# ir_remote_v2.net
KiCad netlist of a schematic drawn in EAGLE
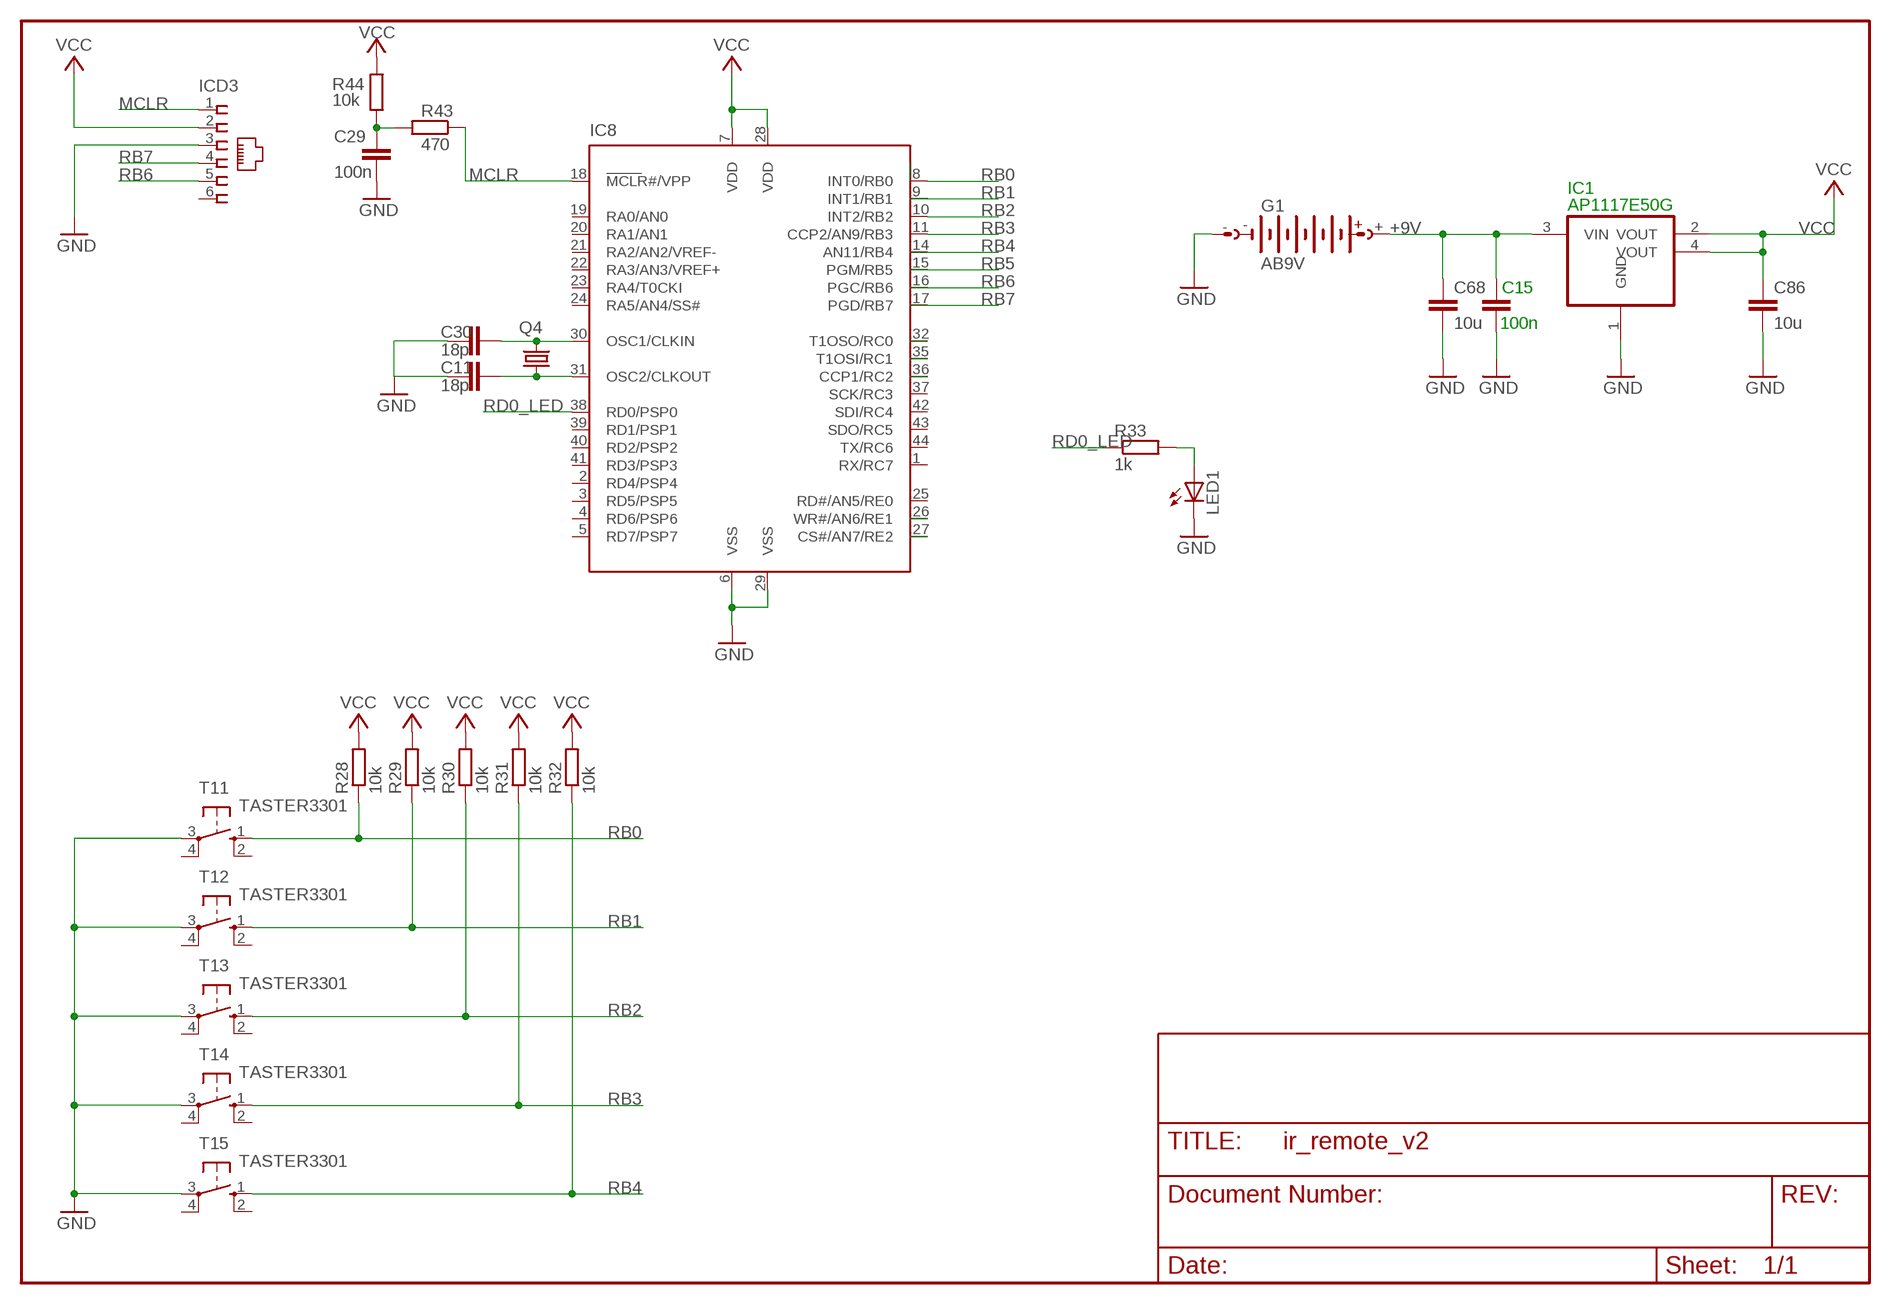
[diagram p0: schematic, sheet 1]

(export (version "E")
  (design (tool "Eeschema 10.0.6"))
  (components
    (comp (ref "C11")
      (value "18p")
      (footprint "eagle-import:C0805")
      (libsource (lib "eagle-import") (part "C-EUC0805"))
    )
    (comp (ref "C15")
      (value "100n")
      (footprint "eagle-import:C0805")
      (libsource (lib "eagle-import") (part "rcl_416_C-EUC0805"))
    )
    (comp (ref "C29")
      (value "100n")
      (footprint "eagle-import:C0805")
      (libsource (lib "eagle-import") (part "C-EUC0805"))
    )
    (comp (ref "C30")
      (value "18p")
      (footprint "eagle-import:C0805")
      (libsource (lib "eagle-import") (part "C-EUC0805"))
    )
    (comp (ref "C68")
      (value "10u")
      (footprint "eagle-import:C0805")
      (libsource (lib "eagle-import") (part "C-EUC0805"))
    )
    (comp (ref "C86")
      (value "10u")
      (footprint "eagle-import:C0805")
      (libsource (lib "eagle-import") (part "C-EUC0805"))
    )
    (comp (ref "G1")
      (value "AB9V")
      (footprint "eagle-import:AB9V")
      (libsource (lib "eagle-import") (part "AB9V"))
    )
    (comp (ref "IC1")
      (value "AP1117E50G")
      (footprint "eagle-import:SOT223")
      (libsource (lib "eagle-import") (part "REG1117-2OUT"))
    )
    (comp (ref "IC8")
      (value "PIC18F4520")
      (footprint "eagle-import:TQFP44")
      (libsource (lib "eagle-import") (part "PIC18F4520"))
    )
    (comp (ref "ICD3")
      (value "520250-3")
      (footprint "eagle-import:520250-3")
      (libsource (lib "eagle-import") (part "520250-3"))
    )
    (comp (ref "LED1")
      (value "LED5MM")
      (footprint "eagle-import:LED5MM")
      (libsource (lib "eagle-import") (part "LED5MM"))
    )
    (comp (ref "Q4")
      (value "CRYTALHC49U-V")
      (footprint "eagle-import:HC49U-V")
      (libsource (lib "eagle-import") (part "CRYTALHC49U-V"))
    )
    (comp (ref "R28")
      (value "10k")
      (footprint "eagle-import:0207_7")
      (libsource (lib "eagle-import") (part "R-EU_0207/7"))
    )
    (comp (ref "R29")
      (value "10k")
      (footprint "eagle-import:0207_7")
      (libsource (lib "eagle-import") (part "R-EU_0207/7"))
    )
    (comp (ref "R30")
      (value "10k")
      (footprint "eagle-import:0207_7")
      (libsource (lib "eagle-import") (part "R-EU_0207/7"))
    )
    (comp (ref "R31")
      (value "10k")
      (footprint "eagle-import:0207_7")
      (libsource (lib "eagle-import") (part "R-EU_0207/7"))
    )
    (comp (ref "R32")
      (value "10k")
      (footprint "eagle-import:0207_7")
      (libsource (lib "eagle-import") (part "R-EU_0207/7"))
    )
    (comp (ref "R33")
      (value "1k")
      (footprint "eagle-import:0207_10")
      (libsource (lib "eagle-import") (part "resistor_R-EU_0207/10"))
    )
    (comp (ref "R43")
      (value "470")
      (footprint "eagle-import:M0805")
      (libsource (lib "eagle-import") (part "R-EU_M0805"))
    )
    (comp (ref "R44")
      (value "10k")
      (footprint "eagle-import:M0805")
      (libsource (lib "eagle-import") (part "R-EU_M0805"))
    )
    (comp (ref "T11")
      (value "TASTER3301")
      (footprint "eagle-import:TASTER3301")
      (libsource (lib "eagle-import") (part "TASTER3301"))
    )
    (comp (ref "T12")
      (value "TASTER3301")
      (footprint "eagle-import:TASTER3301")
      (libsource (lib "eagle-import") (part "TASTER3301"))
    )
    (comp (ref "T13")
      (value "TASTER3301")
      (footprint "eagle-import:TASTER3301")
      (libsource (lib "eagle-import") (part "TASTER3301"))
    )
    (comp (ref "T14")
      (value "TASTER3301")
      (footprint "eagle-import:TASTER3301")
      (libsource (lib "eagle-import") (part "TASTER3301"))
    )
    (comp (ref "T15")
      (value "TASTER3301")
      (footprint "eagle-import:TASTER3301")
      (libsource (lib "eagle-import") (part "TASTER3301"))
    )
  )
  (nets
    (net (code "1") (name "/+9V") (class "Default")
      (node (ref "C15") (pin "1") (pinfunction "1_1") (pintype "passive"))
      (node (ref "C68") (pin "1") (pinfunction "1_1") (pintype "passive"))
      (node (ref "G1") (pin "+") (pinfunction "+_+") (pintype "passive"))
      (node (ref "IC1") (pin "3") (pinfunction "VIN_3") (pintype "input"))
    )
    (net (code "2") (name "/MCLR") (class "Default")
      (node (ref "IC8") (pin "18") (pinfunction "MCLR#/VPP_18") (pintype "input"))
      (node (ref "ICD3") (pin "1") (pinfunction "1_1") (pintype "passive"))
      (node (ref "R43") (pin "1") (pinfunction "1_1") (pintype "passive"))
    )
    (net (code "3") (name "/RB0") (class "Default")
      (node (ref "IC8") (pin "8") (pinfunction "INT0/RB0_8") (pintype "bidirectional"))
      (node (ref "R28") (pin "1") (pinfunction "1_1") (pintype "passive"))
      (node (ref "T11") (pin "1") (pinfunction "S_1") (pintype "passive"))
    )
    (net (code "4") (name "/RB1") (class "Default")
      (node (ref "IC8") (pin "35") (pinfunction "T1OSI/RC1_35") (pintype "bidirectional"))
      (node (ref "IC8") (pin "9") (pinfunction "INT1/RB1_9") (pintype "bidirectional"))
      (node (ref "R29") (pin "1") (pinfunction "1_1") (pintype "passive"))
      (node (ref "T12") (pin "1") (pinfunction "S_1") (pintype "passive"))
    )
    (net (code "5") (name "/RB2") (class "Default")
      (node (ref "IC8") (pin "10") (pinfunction "INT2/RB2_10") (pintype "bidirectional"))
      (node (ref "IC8") (pin "32") (pinfunction "T1OSO/RC0_32") (pintype "bidirectional"))
      (node (ref "R30") (pin "1") (pinfunction "1_1") (pintype "passive"))
      (node (ref "T13") (pin "1") (pinfunction "S_1") (pintype "passive"))
    )
    (net (code "6") (name "/RB3") (class "Default")
      (node (ref "IC8") (pin "11") (pinfunction "CCP2/AN9/RB3_11") (pintype "bidirectional"))
      (node (ref "R31") (pin "1") (pinfunction "1_1") (pintype "passive"))
      (node (ref "T14") (pin "1") (pinfunction "S_1") (pintype "passive"))
    )
    (net (code "7") (name "/RB4") (class "Default")
      (node (ref "IC8") (pin "14") (pinfunction "AN11/RB4_14") (pintype "bidirectional"))
      (node (ref "R32") (pin "1") (pinfunction "1_1") (pintype "passive"))
      (node (ref "T15") (pin "1") (pinfunction "S_1") (pintype "passive"))
    )
    (net (code "8") (name "/RB5") (class "Default")
      (node (ref "IC8") (pin "15") (pinfunction "PGM/RB5_15") (pintype "bidirectional"))
    )
    (net (code "9") (name "/RB6") (class "Default")
      (node (ref "IC8") (pin "16") (pinfunction "PGC/RB6_16") (pintype "bidirectional"))
      (node (ref "ICD3") (pin "5") (pinfunction "5_5") (pintype "passive"))
    )
    (net (code "10") (name "/RB7") (class "Default")
      (node (ref "IC8") (pin "17") (pinfunction "PGD/RB7_17") (pintype "bidirectional"))
      (node (ref "ICD3") (pin "4") (pinfunction "4_4") (pintype "passive"))
    )
    (net (code "11") (name "/RD0_LED") (class "Default")
      (node (ref "IC8") (pin "38") (pinfunction "RD0/PSP0_38") (pintype "bidirectional"))
      (node (ref "R33") (pin "1") (pinfunction "1_1") (pintype "passive"))
    )
    (net (code "12") (name "GND") (class "Default")
      (node (ref "C11") (pin "2") (pinfunction "2_2") (pintype "passive"))
      (node (ref "C15") (pin "2") (pinfunction "2_2") (pintype "passive"))
      (node (ref "C29") (pin "2") (pinfunction "2_2") (pintype "passive"))
      (node (ref "C30") (pin "2") (pinfunction "2_2") (pintype "passive"))
      (node (ref "C68") (pin "2") (pinfunction "2_2") (pintype "passive"))
      (node (ref "C86") (pin "2") (pinfunction "2_2") (pintype "passive"))
      (node (ref "G1") (pin "-") (pinfunction "-_-") (pintype "passive"))
      (node (ref "IC1") (pin "1") (pinfunction "GND_1") (pintype "power_in"))
      (node (ref "IC8") (pin "29") (pinfunction "VSS_29") (pintype "bidirectional"))
      (node (ref "IC8") (pin "6") (pinfunction "VSS_6") (pintype "bidirectional"))
      (node (ref "ICD3") (pin "3") (pinfunction "3_3") (pintype "passive"))
      (node (ref "LED1") (pin "K") (pinfunction "C_K") (pintype "passive"))
      (node (ref "T11") (pin "3") (pinfunction "P_3") (pintype "passive"))
      (node (ref "T12") (pin "3") (pinfunction "P_3") (pintype "passive"))
      (node (ref "T13") (pin "3") (pinfunction "P_3") (pintype "passive"))
      (node (ref "T14") (pin "3") (pinfunction "P_3") (pintype "passive"))
      (node (ref "T15") (pin "3") (pinfunction "P_3") (pintype "passive"))
    )
    (net (code "13") (name "Net-(C29-Pad1)") (class "Default")
      (node (ref "C29") (pin "1") (pinfunction "1_1") (pintype "passive"))
      (node (ref "R43") (pin "2") (pinfunction "2_2") (pintype "passive"))
      (node (ref "R44") (pin "2") (pinfunction "2_2") (pintype "passive"))
    )
    (net (code "14") (name "Net-(IC8-OSC1{slash}CLKIN)") (class "Default")
      (node (ref "C30") (pin "1") (pinfunction "1_1") (pintype "passive"))
      (node (ref "IC8") (pin "30") (pinfunction "OSC1/CLKIN_30") (pintype "input"))
      (node (ref "Q4") (pin "2") (pinfunction "2_2") (pintype "passive"))
    )
    (net (code "15") (name "Net-(IC8-OSC2{slash}CLKOUT)") (class "Default")
      (node (ref "C11") (pin "1") (pinfunction "1_1") (pintype "passive"))
      (node (ref "IC8") (pin "31") (pinfunction "OSC2/CLKOUT_31") (pintype "output"))
      (node (ref "Q4") (pin "1") (pinfunction "1_1") (pintype "passive"))
    )
    (net (code "16") (name "Net-(LED1-PadA)") (class "Default")
      (node (ref "LED1") (pin "A") (pinfunction "A_A") (pintype "passive"))
      (node (ref "R33") (pin "2") (pinfunction "2_2") (pintype "passive"))
    )
    (net (code "17") (name "VCC") (class "Default")
      (node (ref "C86") (pin "1") (pinfunction "1_1") (pintype "passive"))
      (node (ref "IC1") (pin "2") (pinfunction "VOUT_2") (pintype "output"))
      (node (ref "IC1") (pin "4") (pinfunction "VOUT_4") (pintype "bidirectional"))
      (node (ref "IC8") (pin "28") (pinfunction "VDD_28") (pintype "bidirectional"))
      (node (ref "IC8") (pin "7") (pinfunction "VDD_7") (pintype "bidirectional"))
      (node (ref "ICD3") (pin "2") (pinfunction "2_2") (pintype "passive"))
      (node (ref "R28") (pin "2") (pinfunction "2_2") (pintype "passive"))
      (node (ref "R29") (pin "2") (pinfunction "2_2") (pintype "passive"))
      (node (ref "R30") (pin "2") (pinfunction "2_2") (pintype "passive"))
      (node (ref "R31") (pin "2") (pinfunction "2_2") (pintype "passive"))
      (node (ref "R32") (pin "2") (pinfunction "2_2") (pintype "passive"))
      (node (ref "R44") (pin "1") (pinfunction "1_1") (pintype "passive"))
    )
    (net (code "18") (name "unconnected-(IC8-CCP1{slash}RC2-Pad36)") (class "Default")
      (node (ref "IC8") (pin "36") (pinfunction "CCP1/RC2_36") (pintype "bidirectional"))
    )
    (net (code "19") (name "unconnected-(IC8-CS#{slash}AN7{slash}RE2-Pad27)") (class "Default")
      (node (ref "IC8") (pin "27") (pinfunction "CS#/AN7/RE2_27") (pintype "bidirectional"))
    )
    (net (code "20") (name "unconnected-(IC8-RA0{slash}AN0-Pad19)") (class "Default")
      (node (ref "IC8") (pin "19") (pinfunction "RA0/AN0_19") (pintype "bidirectional"))
    )
    (net (code "21") (name "unconnected-(IC8-RA1{slash}AN1-Pad20)") (class "Default")
      (node (ref "IC8") (pin "20") (pinfunction "RA1/AN1_20") (pintype "bidirectional"))
    )
    (net (code "22") (name "unconnected-(IC8-RA2{slash}AN2{slash}VREF--Pad21)") (class "Default")
      (node (ref "IC8") (pin "21") (pinfunction "RA2/AN2/VREF-_21") (pintype "bidirectional"))
    )
    (net (code "23") (name "unconnected-(IC8-RA3{slash}AN3{slash}VREF+-Pad22)") (class "Default")
      (node (ref "IC8") (pin "22") (pinfunction "RA3/AN3/VREF+_22") (pintype "bidirectional"))
    )
    (net (code "24") (name "unconnected-(IC8-RA4{slash}T0CKI-Pad23)") (class "Default")
      (node (ref "IC8") (pin "23") (pinfunction "RA4/T0CKI_23") (pintype "bidirectional"))
    )
    (net (code "25") (name "unconnected-(IC8-RA5{slash}AN4{slash}SS#-Pad24)") (class "Default")
      (node (ref "IC8") (pin "24") (pinfunction "RA5/AN4/SS#_24") (pintype "bidirectional"))
    )
    (net (code "26") (name "unconnected-(IC8-RD#{slash}AN5{slash}RE0-Pad25)") (class "Default")
      (node (ref "IC8") (pin "25") (pinfunction "RD#/AN5/RE0_25") (pintype "bidirectional"))
    )
    (net (code "27") (name "unconnected-(IC8-RD1{slash}PSP1-Pad39)") (class "Default")
      (node (ref "IC8") (pin "39") (pinfunction "RD1/PSP1_39") (pintype "bidirectional"))
    )
    (net (code "28") (name "unconnected-(IC8-RD2{slash}PSP2-Pad40)") (class "Default")
      (node (ref "IC8") (pin "40") (pinfunction "RD2/PSP2_40") (pintype "bidirectional"))
    )
    (net (code "29") (name "unconnected-(IC8-RD3{slash}PSP3-Pad41)") (class "Default")
      (node (ref "IC8") (pin "41") (pinfunction "RD3/PSP3_41") (pintype "bidirectional"))
    )
    (net (code "30") (name "unconnected-(IC8-RD4{slash}PSP4-Pad2)") (class "Default")
      (node (ref "IC8") (pin "2") (pinfunction "RD4/PSP4_2") (pintype "bidirectional"))
    )
    (net (code "31") (name "unconnected-(IC8-RD5{slash}PSP5-Pad3)") (class "Default")
      (node (ref "IC8") (pin "3") (pinfunction "RD5/PSP5_3") (pintype "bidirectional"))
    )
    (net (code "32") (name "unconnected-(IC8-RD6{slash}PSP6-Pad4)") (class "Default")
      (node (ref "IC8") (pin "4") (pinfunction "RD6/PSP6_4") (pintype "bidirectional"))
    )
    (net (code "33") (name "unconnected-(IC8-RD7{slash}PSP7-Pad5)") (class "Default")
      (node (ref "IC8") (pin "5") (pinfunction "RD7/PSP7_5") (pintype "bidirectional"))
    )
    (net (code "34") (name "unconnected-(IC8-RX{slash}RC7-Pad1)") (class "Default")
      (node (ref "IC8") (pin "1") (pinfunction "RX/RC7_1") (pintype "bidirectional"))
    )
    (net (code "35") (name "unconnected-(IC8-SCK{slash}RC3-Pad37)") (class "Default")
      (node (ref "IC8") (pin "37") (pinfunction "SCK/RC3_37") (pintype "bidirectional"))
    )
    (net (code "36") (name "unconnected-(IC8-SDI{slash}RC4-Pad42)") (class "Default")
      (node (ref "IC8") (pin "42") (pinfunction "SDI/RC4_42") (pintype "bidirectional"))
    )
    (net (code "37") (name "unconnected-(IC8-SDO{slash}RC5-Pad43)") (class "Default")
      (node (ref "IC8") (pin "43") (pinfunction "SDO/RC5_43") (pintype "bidirectional"))
    )
    (net (code "38") (name "unconnected-(IC8-TX{slash}RC6-Pad44)") (class "Default")
      (node (ref "IC8") (pin "44") (pinfunction "TX/RC6_44") (pintype "bidirectional"))
    )
    (net (code "39") (name "unconnected-(IC8-WR#{slash}AN6{slash}RE1-Pad26)") (class "Default")
      (node (ref "IC8") (pin "26") (pinfunction "WR#/AN6/RE1_26") (pintype "bidirectional"))
    )
    (net (code "40") (name "unconnected-(ICD3-Pad6)") (class "Default")
      (node (ref "ICD3") (pin "6") (pinfunction "6_6") (pintype "passive"))
    )
    (net (code "41") (name "unconnected-(T11-P1-Pad4)") (class "Default")
      (node (ref "T11") (pin "4") (pinfunction "P1_4") (pintype "passive"))
    )
    (net (code "42") (name "unconnected-(T11-S1-Pad2)") (class "Default")
      (node (ref "T11") (pin "2") (pinfunction "S1_2") (pintype "passive"))
    )
    (net (code "43") (name "unconnected-(T12-P1-Pad4)") (class "Default")
      (node (ref "T12") (pin "4") (pinfunction "P1_4") (pintype "passive"))
    )
    (net (code "44") (name "unconnected-(T12-S1-Pad2)") (class "Default")
      (node (ref "T12") (pin "2") (pinfunction "S1_2") (pintype "passive"))
    )
    (net (code "45") (name "unconnected-(T13-P1-Pad4)") (class "Default")
      (node (ref "T13") (pin "4") (pinfunction "P1_4") (pintype "passive"))
    )
    (net (code "46") (name "unconnected-(T13-S1-Pad2)") (class "Default")
      (node (ref "T13") (pin "2") (pinfunction "S1_2") (pintype "passive"))
    )
    (net (code "47") (name "unconnected-(T14-P1-Pad4)") (class "Default")
      (node (ref "T14") (pin "4") (pinfunction "P1_4") (pintype "passive"))
    )
    (net (code "48") (name "unconnected-(T14-S1-Pad2)") (class "Default")
      (node (ref "T14") (pin "2") (pinfunction "S1_2") (pintype "passive"))
    )
    (net (code "49") (name "unconnected-(T15-P1-Pad4)") (class "Default")
      (node (ref "T15") (pin "4") (pinfunction "P1_4") (pintype "passive"))
    )
    (net (code "50") (name "unconnected-(T15-S1-Pad2)") (class "Default")
      (node (ref "T15") (pin "2") (pinfunction "S1_2") (pintype "passive"))
    )
  )
)
